# sensor_sheet.net
KiCad netlist of a schematic drawn in Altium Designer
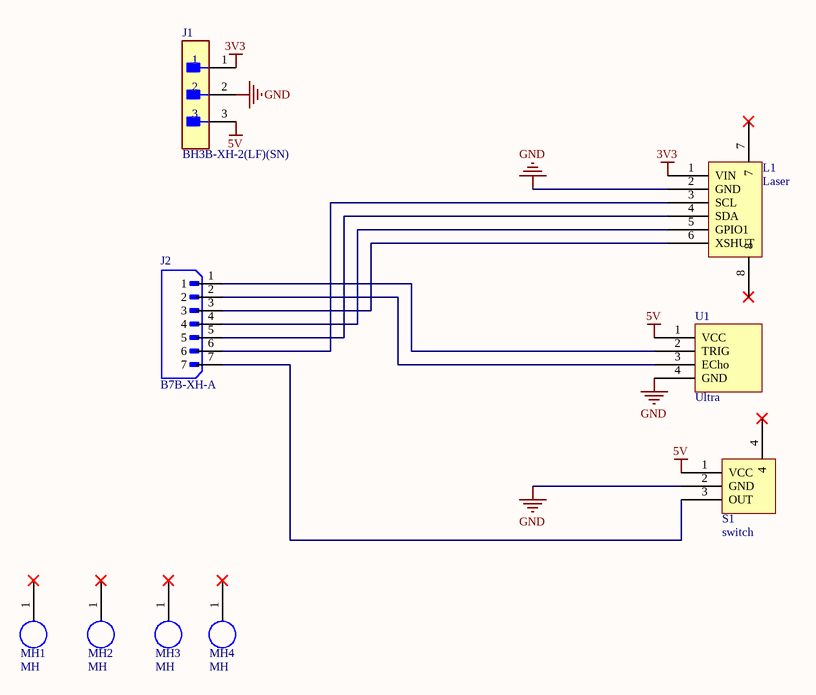
[diagram p0: sensor_sheet.SchDoc]

(export (version "E")
  (design (tool "Eeschema 10.0.6"))
  (components
    (comp (ref "J1")
      (value "BH3B-XH-2(LF)(SN)")
      (footprint "FP-BH3B-XH-2_LF_SN-MFG")
      (description "CONN HEADER VERT 3POS 2.5MM")
      (libsource (lib "Altium Content Vault") (part "0d3f023dd272f625e17a2be33dea85f"))
    )
    (comp (ref "J2")
      (value "B7B-XH-A")
      (footprint "JST_B7B-XH-A")
      (description "Connector Header Through Hole 7 position 0.098 (2.50mm)")
      (fields (field (name "MF") "JST Sales"))
      (libsource (lib "sensor_s") (part "B7B-XH-A"))
    )
    (comp (ref "L1") (value "Laser") (footprint "laser_1") (libsource (lib "sensor_s") (part "Laser_1")))
    (comp (ref "MH1") (value "MH") (footprint "MH") (libsource (lib "sensor_s") (part "MH")))
    (comp (ref "MH2") (value "MH") (footprint "MH") (libsource (lib "sensor_s") (part "MH")))
    (comp (ref "MH3") (value "MH") (footprint "MH") (libsource (lib "sensor_s") (part "MH")))
    (comp (ref "MH4") (value "MH") (footprint "MH") (libsource (lib "sensor_s") (part "MH")))
    (comp (ref "S1") (value "switch") (footprint "Switch") (libsource (lib "sensor_s") (part "Switch")))
    (comp (ref "U1") (value "Ultra") (footprint "UltraSoic") (libsource (lib "sensor_s") (part "ULTRA")))
  )
  (nets
    (net (code "1") (name "3V3") (class "Default")
      (node (ref "J1") (pin "1") (pinfunction "1_1") (pintype "passive"))
      (node (ref "L1") (pin "1") (pinfunction "VIN_1") (pintype "passive"))
    )
    (net (code "2") (name "5V") (class "Default")
      (node (ref "J1") (pin "3") (pinfunction "3_3") (pintype "passive"))
      (node (ref "S1") (pin "1") (pinfunction "VCC_1") (pintype "passive"))
      (node (ref "U1") (pin "1") (pinfunction "VCC_1") (pintype "passive"))
    )
    (net (code "3") (name "GND") (class "Default")
      (node (ref "J1") (pin "2") (pinfunction "2_2") (pintype "passive"))
      (node (ref "L1") (pin "2") (pinfunction "GND_2") (pintype "passive"))
      (node (ref "S1") (pin "2") (pinfunction "GND_2") (pintype "passive"))
      (node (ref "U1") (pin "4") (pinfunction "GND_4") (pintype "passive"))
    )
    (net (code "4") (name "Net-(L1-GPIO1)") (class "Default")
      (node (ref "J2") (pin "4") (pinfunction "4_4") (pintype "passive"))
      (node (ref "L1") (pin "5") (pinfunction "GPIO1_5") (pintype "passive"))
    )
    (net (code "5") (name "Net-(L1-SCL)") (class "Default")
      (node (ref "J2") (pin "6") (pinfunction "6_6") (pintype "passive"))
      (node (ref "L1") (pin "3") (pinfunction "SCL_3") (pintype "passive"))
    )
    (net (code "6") (name "Net-(L1-SDA)") (class "Default")
      (node (ref "J2") (pin "5") (pinfunction "5_5") (pintype "passive"))
      (node (ref "L1") (pin "4") (pinfunction "SDA_4") (pintype "passive"))
    )
    (net (code "7") (name "Net-(L1-XSHUT)") (class "Default")
      (node (ref "J2") (pin "3") (pinfunction "3_3") (pintype "passive"))
      (node (ref "L1") (pin "6") (pinfunction "XSHUT_6") (pintype "passive"))
    )
    (net (code "8") (name "Net-(S1-OUT)") (class "Default")
      (node (ref "J2") (pin "7") (pinfunction "7_7") (pintype "passive"))
      (node (ref "S1") (pin "3") (pinfunction "OUT_3") (pintype "passive"))
    )
    (net (code "9") (name "Net-(U1-ECho)") (class "Default")
      (node (ref "J2") (pin "2") (pinfunction "2_2") (pintype "passive"))
      (node (ref "U1") (pin "3") (pinfunction "ECho_3") (pintype "passive"))
    )
    (net (code "10") (name "Net-(U1-TRIG)") (class "Default")
      (node (ref "J2") (pin "1") (pinfunction "1_1") (pintype "passive"))
      (node (ref "U1") (pin "2") (pinfunction "TRIG_2") (pintype "passive"))
    )
    (net (code "11") (name "unconnected-(L1-Pad7)") (class "Default")
      (node (ref "L1") (pin "7") (pinfunction "7_7") (pintype "passive+no_connect"))
    )
    (net (code "12") (name "unconnected-(L1-Pad8)") (class "Default")
      (node (ref "L1") (pin "8") (pinfunction "8_8") (pintype "passive+no_connect"))
    )
    (net (code "13") (name "unconnected-(MH1-Pad1)") (class "Default")
      (node (ref "MH1") (pin "1") (pinfunction "1_1") (pintype "passive+no_connect"))
    )
    (net (code "14") (name "unconnected-(MH2-Pad1)") (class "Default")
      (node (ref "MH2") (pin "1") (pinfunction "1_1") (pintype "passive+no_connect"))
    )
    (net (code "15") (name "unconnected-(MH3-Pad1)") (class "Default")
      (node (ref "MH3") (pin "1") (pinfunction "1_1") (pintype "passive+no_connect"))
    )
    (net (code "16") (name "unconnected-(MH4-Pad1)") (class "Default")
      (node (ref "MH4") (pin "1") (pinfunction "1_1") (pintype "passive+no_connect"))
    )
    (net (code "17") (name "unconnected-(S1-Pad4)") (class "Default")
      (node (ref "S1") (pin "4") (pinfunction "4_4") (pintype "passive+no_connect"))
    )
  )
)
